# 04_ALU.net
KiCad netlist of a schematic drawn in EAGLE
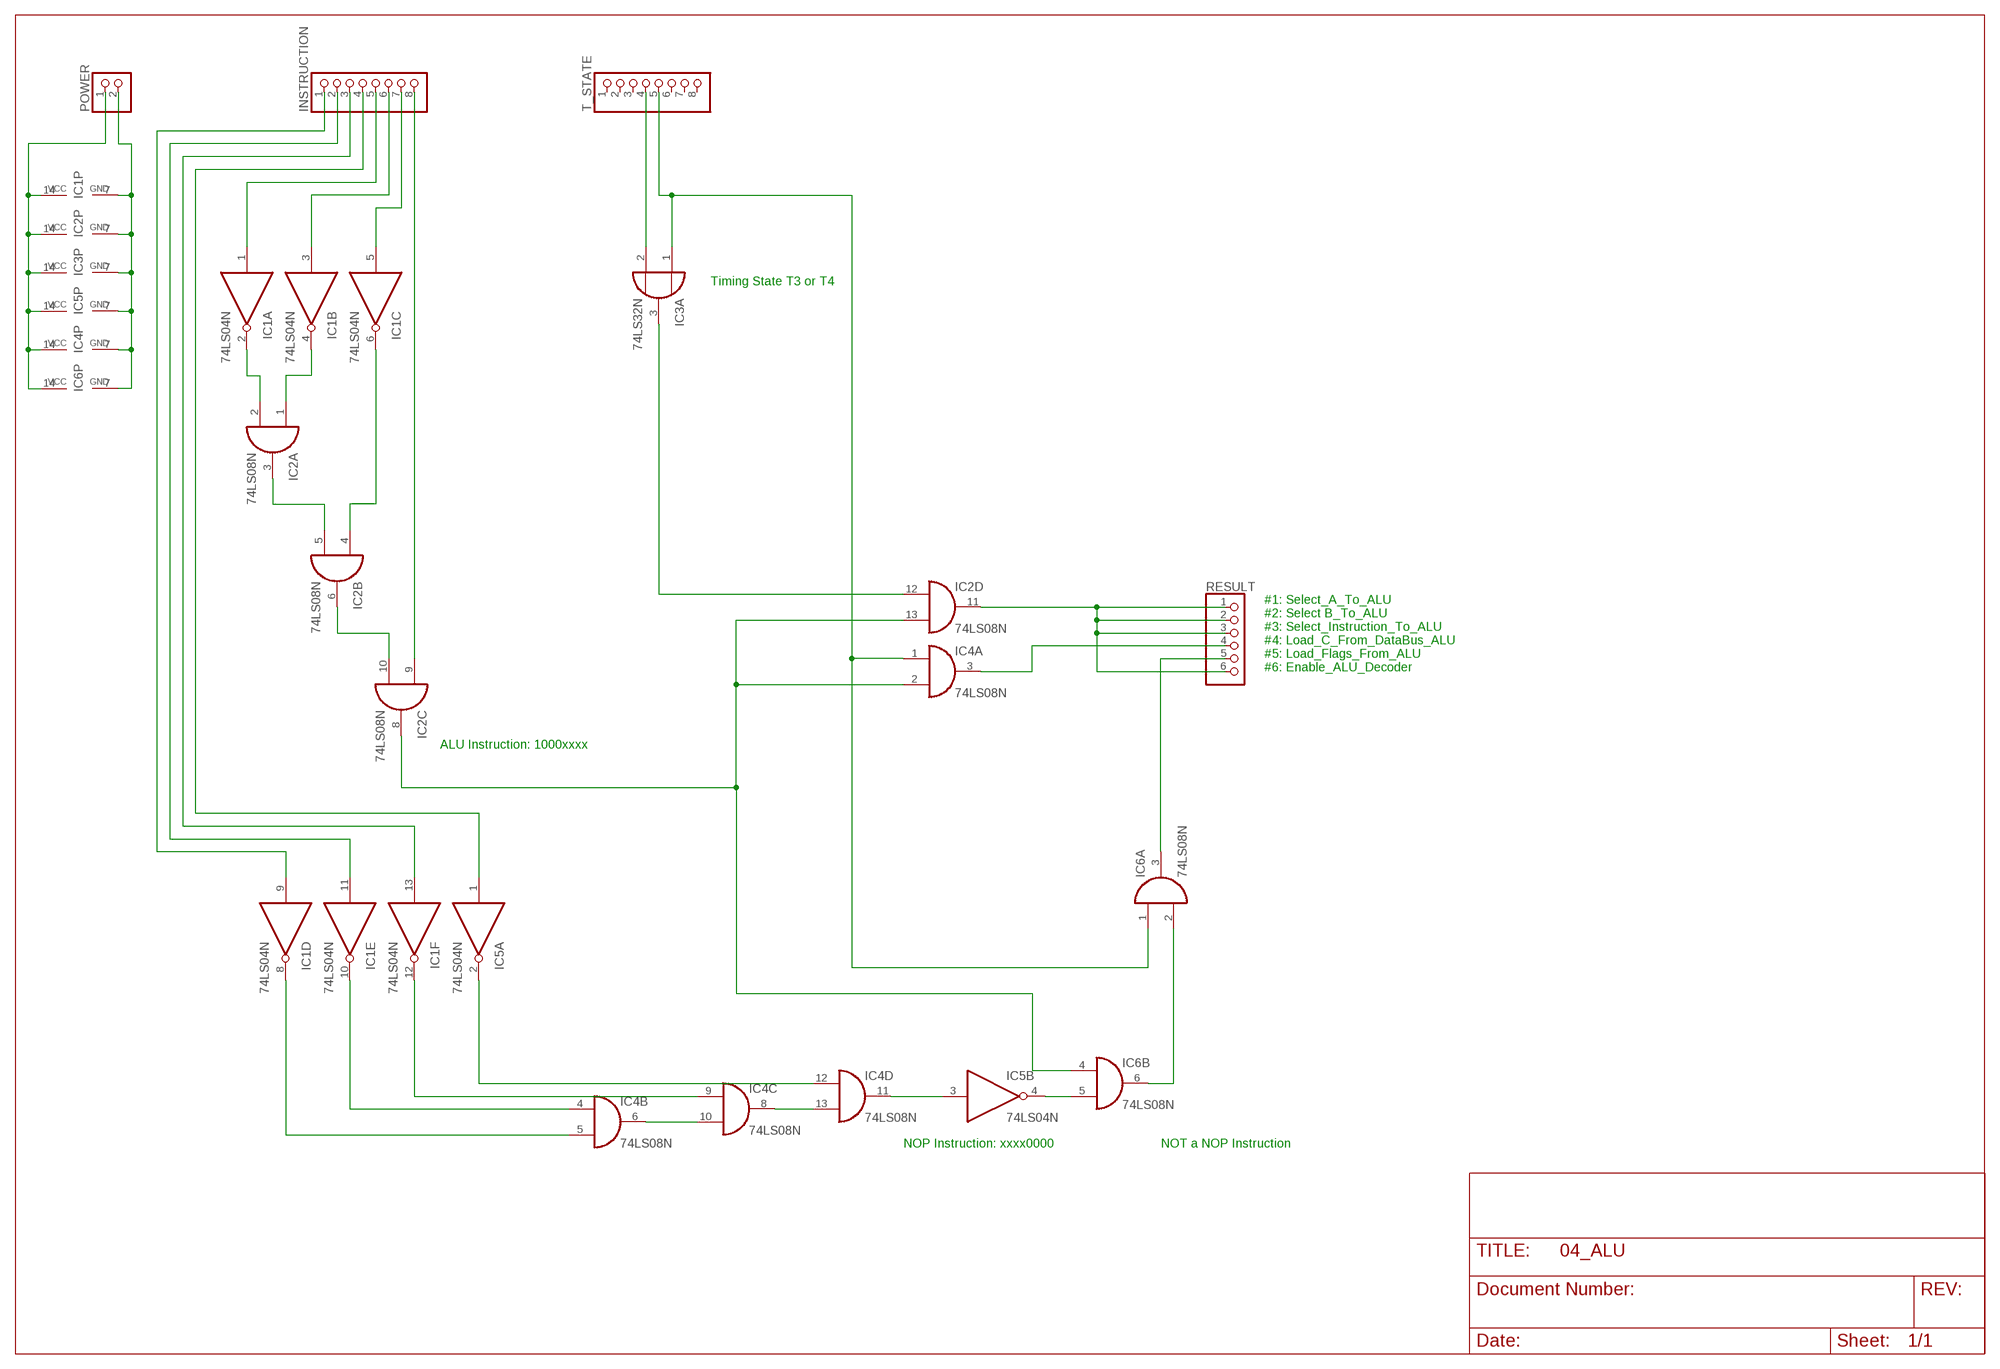
[diagram p0: schematic, sheet 1]

(export (version "E")
  (design (tool "Eeschema 10.0.6"))
  (components
    (comp (ref "IC1")
      (value "74LS04N")
      (footprint "eagle-import:DIL14")
      (libsource (lib "eagle-import") (part "7404NLS"))
    )
    (comp (ref "IC2")
      (value "74LS08N")
      (footprint "eagle-import:DIL14")
      (libsource (lib "eagle-import") (part "7408NLS"))
    )
    (comp (ref "IC3")
      (value "74LS32N")
      (footprint "eagle-import:DIL14")
      (libsource (lib "eagle-import") (part "7432NLS"))
    )
    (comp (ref "IC4")
      (value "74LS08N")
      (footprint "eagle-import:DIL14")
      (libsource (lib "eagle-import") (part "7408NLS"))
    )
    (comp (ref "IC5")
      (value "74LS04N")
      (footprint "eagle-import:DIL14")
      (libsource (lib "eagle-import") (part "7404NLS"))
    )
    (comp (ref "IC6")
      (value "74LS08N")
      (footprint "eagle-import:DIL14")
      (libsource (lib "eagle-import") (part "7408NLS"))
    )
    (comp (ref "INSTRUCTION")
      (value "PINHD-1X8")
      (footprint "eagle-import:1X08")
      (libsource (lib "eagle-import") (part "PINHD-1X8"))
    )
    (comp (ref "POWER")
      (value "PINHD-1X2")
      (footprint "eagle-import:1X02")
      (libsource (lib "eagle-import") (part "PINHD-1X2"))
    )
    (comp (ref "RESULT")
      (value "PINHD-1X6")
      (footprint "eagle-import:1X06")
      (libsource (lib "eagle-import") (part "PINHD-1X6"))
    )
    (comp (ref "T_STATE")
      (value "PINHD-1X8")
      (footprint "eagle-import:1X08")
      (libsource (lib "eagle-import") (part "PINHD-1X8"))
    )
  )
  (nets
    (net (code "1") (name "Net-(IC1A-I)") (class "Default")
      (node (ref "IC1") (pin "1") (pinfunction "I_1") (pintype "input"))
      (node (ref "INSTRUCTION") (pin "5") (pinfunction "5_5") (pintype "passive"))
    )
    (net (code "2") (name "Net-(IC1A-O)") (class "Default")
      (node (ref "IC1") (pin "2") (pinfunction "O_2") (pintype "output"))
      (node (ref "IC2") (pin "2") (pinfunction "I1_2") (pintype "input"))
    )
    (net (code "3") (name "Net-(IC1B-I)") (class "Default")
      (node (ref "IC1") (pin "3") (pinfunction "I_3") (pintype "input"))
      (node (ref "INSTRUCTION") (pin "6") (pinfunction "6_6") (pintype "passive"))
    )
    (net (code "4") (name "Net-(IC1B-O)") (class "Default")
      (node (ref "IC1") (pin "4") (pinfunction "O_4") (pintype "output"))
      (node (ref "IC2") (pin "1") (pinfunction "I0_1") (pintype "input"))
    )
    (net (code "5") (name "Net-(IC1C-I)") (class "Default")
      (node (ref "IC1") (pin "5") (pinfunction "I_5") (pintype "input"))
      (node (ref "INSTRUCTION") (pin "7") (pinfunction "7_7") (pintype "passive"))
    )
    (net (code "6") (name "Net-(IC1C-O)") (class "Default")
      (node (ref "IC1") (pin "6") (pinfunction "O_6") (pintype "output"))
      (node (ref "IC2") (pin "4") (pinfunction "I0_4") (pintype "input"))
    )
    (net (code "7") (name "Net-(IC1D-I)") (class "Default")
      (node (ref "IC1") (pin "9") (pinfunction "I_9") (pintype "input"))
      (node (ref "INSTRUCTION") (pin "1") (pinfunction "1_1") (pintype "passive"))
    )
    (net (code "8") (name "Net-(IC1D-O)") (class "Default")
      (node (ref "IC1") (pin "8") (pinfunction "O_8") (pintype "output"))
      (node (ref "IC4") (pin "5") (pinfunction "I1_5") (pintype "input"))
    )
    (net (code "9") (name "Net-(IC1E-I)") (class "Default")
      (node (ref "IC1") (pin "11") (pinfunction "I_11") (pintype "input"))
      (node (ref "INSTRUCTION") (pin "2") (pinfunction "2_2") (pintype "passive"))
    )
    (net (code "10") (name "Net-(IC1E-O)") (class "Default")
      (node (ref "IC1") (pin "10") (pinfunction "O_10") (pintype "output"))
      (node (ref "IC4") (pin "4") (pinfunction "I0_4") (pintype "input"))
    )
    (net (code "11") (name "Net-(IC1F-I)") (class "Default")
      (node (ref "IC1") (pin "13") (pinfunction "I_13") (pintype "input"))
      (node (ref "INSTRUCTION") (pin "3") (pinfunction "3_3") (pintype "passive"))
    )
    (net (code "12") (name "Net-(IC1F-O)") (class "Default")
      (node (ref "IC1") (pin "12") (pinfunction "O_12") (pintype "output"))
      (node (ref "IC4") (pin "9") (pinfunction "I0_9") (pintype "input"))
    )
    (net (code "13") (name "Net-(IC1G-GND)") (class "Default")
      (node (ref "IC1") (pin "7") (pinfunction "GND_7") (pintype "power_in"))
      (node (ref "IC2") (pin "7") (pinfunction "GND_7") (pintype "power_in"))
      (node (ref "IC3") (pin "7") (pinfunction "GND_7") (pintype "power_in"))
      (node (ref "IC4") (pin "7") (pinfunction "GND_7") (pintype "power_in"))
      (node (ref "IC5") (pin "7") (pinfunction "GND_7") (pintype "power_in"))
      (node (ref "IC6") (pin "7") (pinfunction "GND_7") (pintype "power_in"))
      (node (ref "POWER") (pin "2") (pinfunction "2_2") (pintype "passive"))
    )
    (net (code "14") (name "Net-(IC1G-VCC)") (class "Default")
      (node (ref "IC1") (pin "14") (pinfunction "VCC_14") (pintype "power_in"))
      (node (ref "IC2") (pin "14") (pinfunction "VCC_14") (pintype "power_in"))
      (node (ref "IC3") (pin "14") (pinfunction "VCC_14") (pintype "power_in"))
      (node (ref "IC4") (pin "14") (pinfunction "VCC_14") (pintype "power_in"))
      (node (ref "IC5") (pin "14") (pinfunction "VCC_14") (pintype "power_in"))
      (node (ref "IC6") (pin "14") (pinfunction "VCC_14") (pintype "power_in"))
      (node (ref "POWER") (pin "1") (pinfunction "1_1") (pintype "passive"))
    )
    (net (code "15") (name "Net-(IC2A-O)") (class "Default")
      (node (ref "IC2") (pin "3") (pinfunction "O_3") (pintype "output"))
      (node (ref "IC2") (pin "5") (pinfunction "I1_5") (pintype "input"))
    )
    (net (code "16") (name "Net-(IC2B-O)") (class "Default")
      (node (ref "IC2") (pin "10") (pinfunction "I1_10") (pintype "input"))
      (node (ref "IC2") (pin "6") (pinfunction "O_6") (pintype "output"))
    )
    (net (code "17") (name "Net-(IC2C-I0)") (class "Default")
      (node (ref "IC2") (pin "9") (pinfunction "I0_9") (pintype "input"))
      (node (ref "INSTRUCTION") (pin "8") (pinfunction "8_8") (pintype "passive"))
    )
    (net (code "18") (name "Net-(IC2C-O)") (class "Default")
      (node (ref "IC2") (pin "13") (pinfunction "I1_13") (pintype "input"))
      (node (ref "IC2") (pin "8") (pinfunction "O_8") (pintype "output"))
      (node (ref "IC4") (pin "2") (pinfunction "I1_2") (pintype "input"))
      (node (ref "IC6") (pin "4") (pinfunction "I0_4") (pintype "input"))
    )
    (net (code "19") (name "Net-(IC2D-I0)") (class "Default")
      (node (ref "IC2") (pin "12") (pinfunction "I0_12") (pintype "input"))
      (node (ref "IC3") (pin "3") (pinfunction "O_3") (pintype "output"))
    )
    (net (code "20") (name "Net-(IC2D-O)") (class "Default")
      (node (ref "IC2") (pin "11") (pinfunction "O_11") (pintype "output"))
      (node (ref "RESULT") (pin "1") (pinfunction "1_1") (pintype "passive"))
      (node (ref "RESULT") (pin "2") (pinfunction "2_2") (pintype "passive"))
      (node (ref "RESULT") (pin "3") (pinfunction "3_3") (pintype "passive"))
      (node (ref "RESULT") (pin "6") (pinfunction "6_6") (pintype "passive"))
    )
    (net (code "21") (name "Net-(IC3A-I0)") (class "Default")
      (node (ref "IC3") (pin "1") (pinfunction "I0_1") (pintype "input"))
      (node (ref "IC4") (pin "1") (pinfunction "I0_1") (pintype "input"))
      (node (ref "IC6") (pin "1") (pinfunction "I0_1") (pintype "input"))
      (node (ref "T_STATE") (pin "5") (pinfunction "5_5") (pintype "passive"))
    )
    (net (code "22") (name "Net-(IC3A-I1)") (class "Default")
      (node (ref "IC3") (pin "2") (pinfunction "I1_2") (pintype "input"))
      (node (ref "T_STATE") (pin "4") (pinfunction "4_4") (pintype "passive"))
    )
    (net (code "23") (name "Net-(IC4A-O)") (class "Default")
      (node (ref "IC4") (pin "3") (pinfunction "O_3") (pintype "output"))
      (node (ref "RESULT") (pin "4") (pinfunction "4_4") (pintype "passive"))
    )
    (net (code "24") (name "Net-(IC4B-O)") (class "Default")
      (node (ref "IC4") (pin "10") (pinfunction "I1_10") (pintype "input"))
      (node (ref "IC4") (pin "6") (pinfunction "O_6") (pintype "output"))
    )
    (net (code "25") (name "Net-(IC4C-O)") (class "Default")
      (node (ref "IC4") (pin "13") (pinfunction "I1_13") (pintype "input"))
      (node (ref "IC4") (pin "8") (pinfunction "O_8") (pintype "output"))
    )
    (net (code "26") (name "Net-(IC4D-I0)") (class "Default")
      (node (ref "IC4") (pin "12") (pinfunction "I0_12") (pintype "input"))
      (node (ref "IC5") (pin "2") (pinfunction "O_2") (pintype "output"))
    )
    (net (code "27") (name "Net-(IC4D-O)") (class "Default")
      (node (ref "IC4") (pin "11") (pinfunction "O_11") (pintype "output"))
      (node (ref "IC5") (pin "3") (pinfunction "I_3") (pintype "input"))
    )
    (net (code "28") (name "Net-(IC5A-I)") (class "Default")
      (node (ref "IC5") (pin "1") (pinfunction "I_1") (pintype "input"))
      (node (ref "INSTRUCTION") (pin "4") (pinfunction "4_4") (pintype "passive"))
    )
    (net (code "29") (name "Net-(IC5B-O)") (class "Default")
      (node (ref "IC5") (pin "4") (pinfunction "O_4") (pintype "output"))
      (node (ref "IC6") (pin "5") (pinfunction "I1_5") (pintype "input"))
    )
    (net (code "30") (name "Net-(IC6A-I1)") (class "Default")
      (node (ref "IC6") (pin "2") (pinfunction "I1_2") (pintype "input"))
      (node (ref "IC6") (pin "6") (pinfunction "O_6") (pintype "output"))
    )
    (net (code "31") (name "Net-(IC6A-O)") (class "Default")
      (node (ref "IC6") (pin "3") (pinfunction "O_3") (pintype "output"))
      (node (ref "RESULT") (pin "5") (pinfunction "5_5") (pintype "passive"))
    )
    (net (code "32") (name "unconnected-(T_STATE-Pad1)") (class "Default")
      (node (ref "T_STATE") (pin "1") (pinfunction "1_1") (pintype "passive"))
    )
    (net (code "33") (name "unconnected-(T_STATE-Pad2)") (class "Default")
      (node (ref "T_STATE") (pin "2") (pinfunction "2_2") (pintype "passive"))
    )
    (net (code "34") (name "unconnected-(T_STATE-Pad3)") (class "Default")
      (node (ref "T_STATE") (pin "3") (pinfunction "3_3") (pintype "passive"))
    )
    (net (code "35") (name "unconnected-(T_STATE-Pad6)") (class "Default")
      (node (ref "T_STATE") (pin "6") (pinfunction "6_6") (pintype "passive"))
    )
    (net (code "36") (name "unconnected-(T_STATE-Pad7)") (class "Default")
      (node (ref "T_STATE") (pin "7") (pinfunction "7_7") (pintype "passive"))
    )
    (net (code "37") (name "unconnected-(T_STATE-Pad8)") (class "Default")
      (node (ref "T_STATE") (pin "8") (pinfunction "8_8") (pintype "passive"))
    )
  )
)
